# 16n.net
KiCad netlist of a schematic drawn in EAGLE
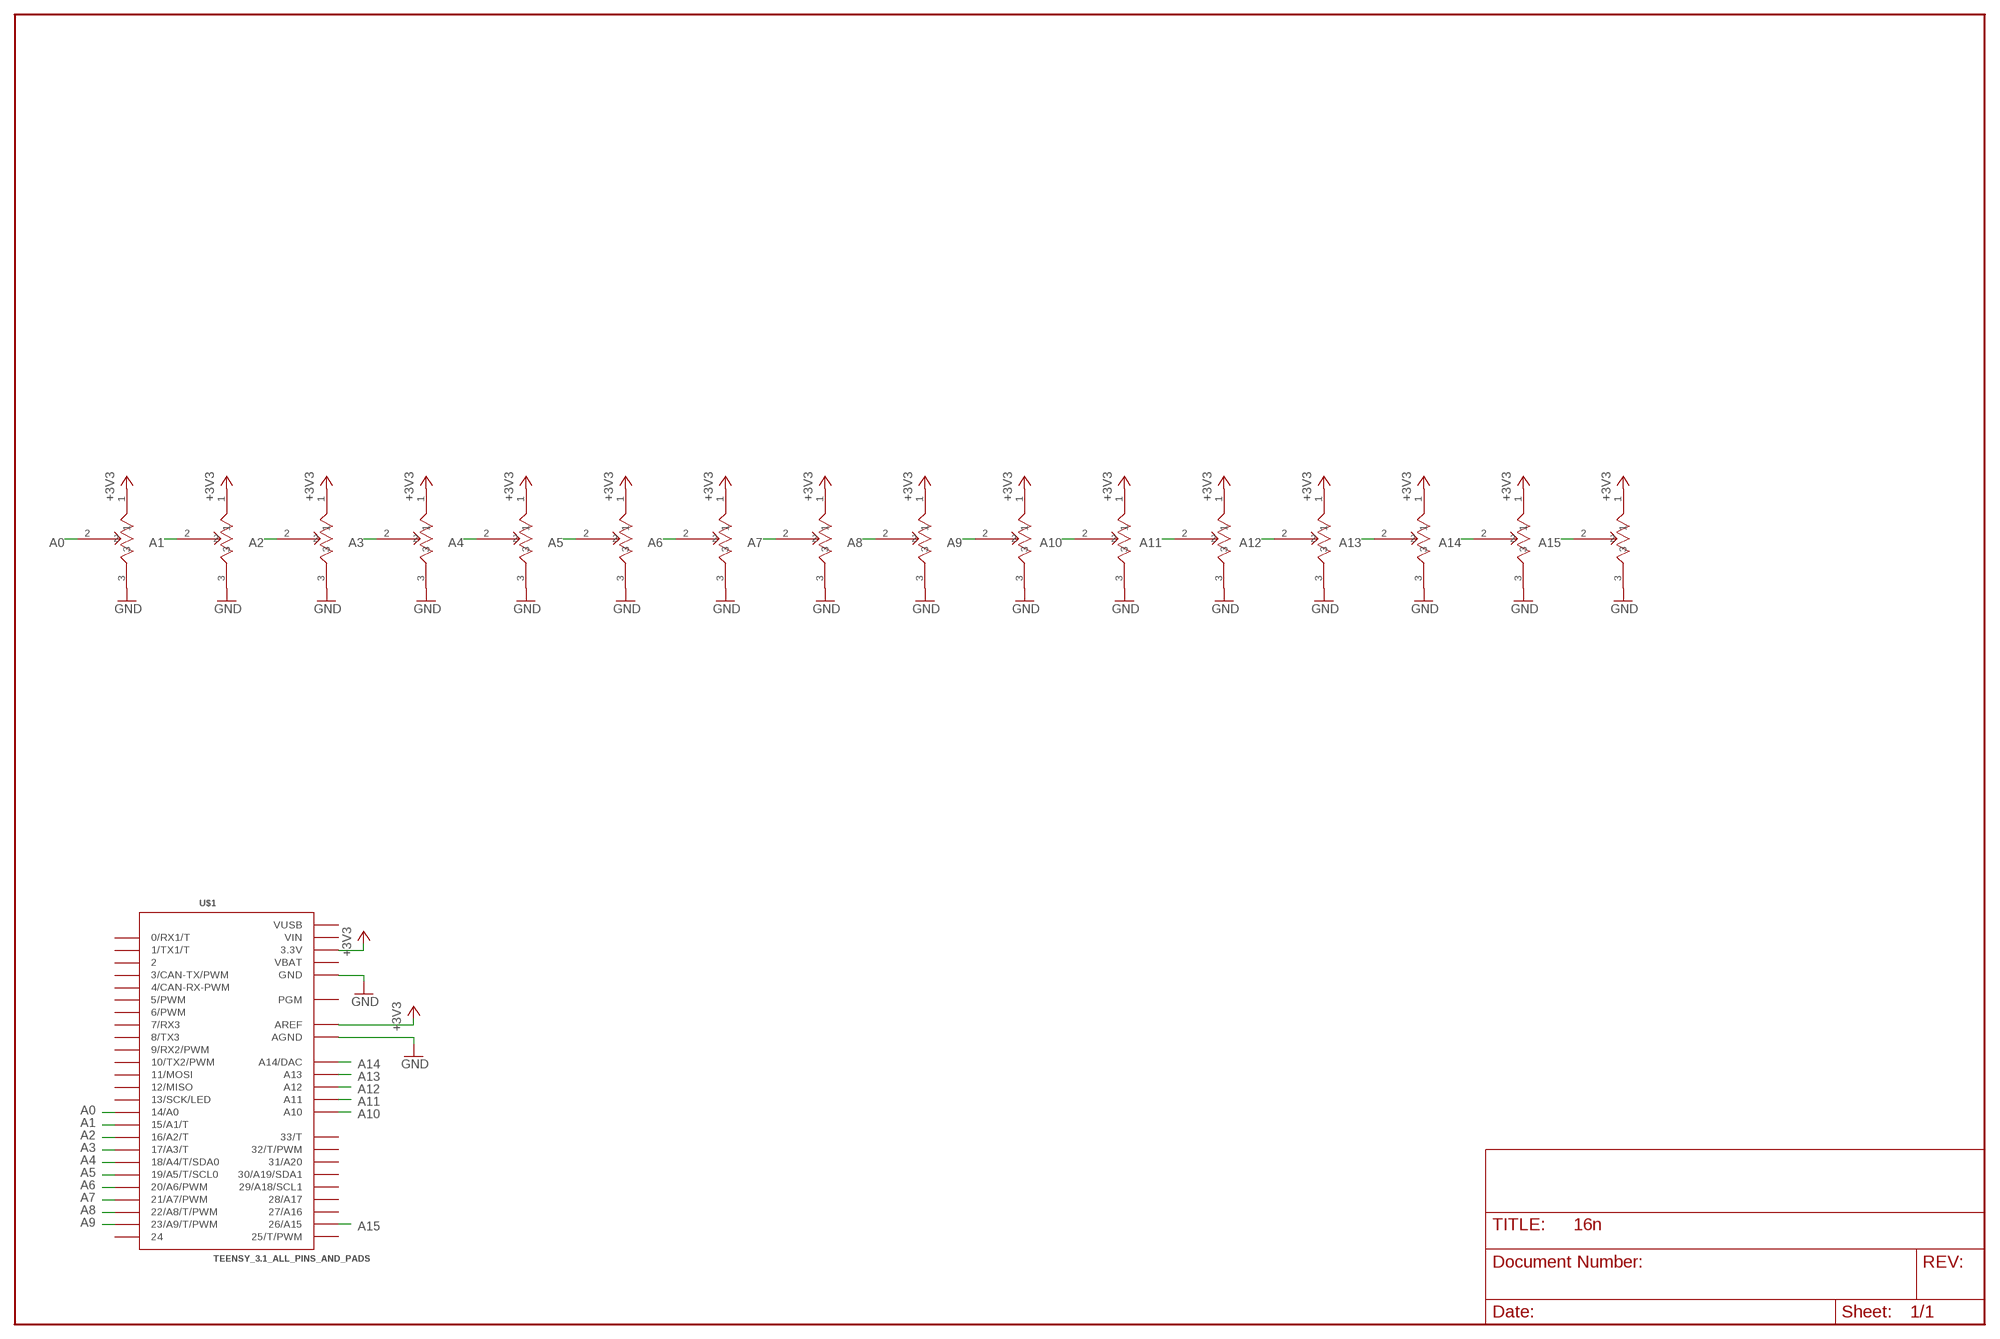
[diagram p0: schematic, sheet 1]

(export (version "E")
  (design (tool "Eeschema 10.0.6"))
  (components
    (comp (ref "U$1")
      (value "TEENSY_3.1_ALL_PINS_AND_PADS")
      (footprint "eagle-import:TEENSY_3.1_ALLPINS")
      (libsource (lib "eagle-import") (part "TEENSY_3.1_ALL_PINS_AND_PADS"))
    )
    (comp (ref "U$2")
      (value "SLIDEPOT-ALPS-60MM")
      (footprint "eagle-import:RS6011SP600")
      (libsource (lib "eagle-import") (part "SLIDEPOT-ALPS-60MM"))
    )
    (comp (ref "U$3")
      (value "SLIDEPOT-ALPS-60MM")
      (footprint "eagle-import:RS6011SP600")
      (libsource (lib "eagle-import") (part "SLIDEPOT-ALPS-60MM"))
    )
    (comp (ref "U$4")
      (value "SLIDEPOT-ALPS-60MM")
      (footprint "eagle-import:RS6011SP600")
      (libsource (lib "eagle-import") (part "SLIDEPOT-ALPS-60MM"))
    )
    (comp (ref "U$5")
      (value "SLIDEPOT-ALPS-60MM")
      (footprint "eagle-import:RS6011SP600")
      (libsource (lib "eagle-import") (part "SLIDEPOT-ALPS-60MM"))
    )
    (comp (ref "U$6")
      (value "SLIDEPOT-ALPS-60MM")
      (footprint "eagle-import:RS6011SP600")
      (libsource (lib "eagle-import") (part "SLIDEPOT-ALPS-60MM"))
    )
    (comp (ref "U$7")
      (value "SLIDEPOT-ALPS-60MM")
      (footprint "eagle-import:RS6011SP600")
      (libsource (lib "eagle-import") (part "SLIDEPOT-ALPS-60MM"))
    )
    (comp (ref "U$8")
      (value "SLIDEPOT-ALPS-60MM")
      (footprint "eagle-import:RS6011SP600")
      (libsource (lib "eagle-import") (part "SLIDEPOT-ALPS-60MM"))
    )
    (comp (ref "U$9")
      (value "SLIDEPOT-ALPS-60MM")
      (footprint "eagle-import:RS6011SP600")
      (libsource (lib "eagle-import") (part "SLIDEPOT-ALPS-60MM"))
    )
    (comp (ref "U$10")
      (value "SLIDEPOT-ALPS-60MM")
      (footprint "eagle-import:RS6011SP600")
      (libsource (lib "eagle-import") (part "SLIDEPOT-ALPS-60MM"))
    )
    (comp (ref "U$11")
      (value "SLIDEPOT-ALPS-60MM")
      (footprint "eagle-import:RS6011SP600")
      (libsource (lib "eagle-import") (part "SLIDEPOT-ALPS-60MM"))
    )
    (comp (ref "U$12")
      (value "SLIDEPOT-ALPS-60MM")
      (footprint "eagle-import:RS6011SP600")
      (libsource (lib "eagle-import") (part "SLIDEPOT-ALPS-60MM"))
    )
    (comp (ref "U$13")
      (value "SLIDEPOT-ALPS-60MM")
      (footprint "eagle-import:RS6011SP600")
      (libsource (lib "eagle-import") (part "SLIDEPOT-ALPS-60MM"))
    )
    (comp (ref "U$14")
      (value "SLIDEPOT-ALPS-60MM")
      (footprint "eagle-import:RS6011SP600")
      (libsource (lib "eagle-import") (part "SLIDEPOT-ALPS-60MM"))
    )
    (comp (ref "U$15")
      (value "SLIDEPOT-ALPS-60MM")
      (footprint "eagle-import:RS6011SP600")
      (libsource (lib "eagle-import") (part "SLIDEPOT-ALPS-60MM"))
    )
    (comp (ref "U$16")
      (value "SLIDEPOT-ALPS-60MM")
      (footprint "eagle-import:RS6011SP600")
      (libsource (lib "eagle-import") (part "SLIDEPOT-ALPS-60MM"))
    )
    (comp (ref "U$17")
      (value "SLIDEPOT-ALPS-60MM")
      (footprint "eagle-import:RS6011SP600")
      (libsource (lib "eagle-import") (part "SLIDEPOT-ALPS-60MM"))
    )
  )
  (nets
    (net (code "1") (name "+3V3") (class "Default")
      (node (ref "U$1") (pin "3.3V") (pinfunction "3.3V_3.3V") (pintype "power_in"))
      (node (ref "U$1") (pin "3.3V1") (pinfunction "3.3V_3.3V1") (pintype "power_in"))
      (node (ref "U$1") (pin "3.3V2") (pinfunction "3.3V_3.3V2") (pintype "power_in"))
      (node (ref "U$1") (pin "AREF") (pinfunction "AREF_AREF") (pintype "power_in"))
      (node (ref "U$10") (pin "1") (pinfunction "1_1") (pintype "bidirectional"))
      (node (ref "U$11") (pin "1") (pinfunction "1_1") (pintype "bidirectional"))
      (node (ref "U$12") (pin "1") (pinfunction "1_1") (pintype "bidirectional"))
      (node (ref "U$13") (pin "1") (pinfunction "1_1") (pintype "bidirectional"))
      (node (ref "U$14") (pin "1") (pinfunction "1_1") (pintype "bidirectional"))
      (node (ref "U$15") (pin "1") (pinfunction "1_1") (pintype "bidirectional"))
      (node (ref "U$16") (pin "1") (pinfunction "1_1") (pintype "bidirectional"))
      (node (ref "U$17") (pin "1") (pinfunction "1_1") (pintype "bidirectional"))
      (node (ref "U$2") (pin "1") (pinfunction "1_1") (pintype "bidirectional"))
      (node (ref "U$3") (pin "1") (pinfunction "1_1") (pintype "bidirectional"))
      (node (ref "U$4") (pin "1") (pinfunction "1_1") (pintype "bidirectional"))
      (node (ref "U$5") (pin "1") (pinfunction "1_1") (pintype "bidirectional"))
      (node (ref "U$6") (pin "1") (pinfunction "1_1") (pintype "bidirectional"))
      (node (ref "U$7") (pin "1") (pinfunction "1_1") (pintype "bidirectional"))
      (node (ref "U$8") (pin "1") (pinfunction "1_1") (pintype "bidirectional"))
      (node (ref "U$9") (pin "1") (pinfunction "1_1") (pintype "bidirectional"))
    )
    (net (code "2") (name "/A0") (class "Default")
      (node (ref "U$1") (pin "14/A0") (pinfunction "14/A0_14/A0") (pintype "bidirectional"))
      (node (ref "U$2") (pin "2") (pinfunction "2_2") (pintype "bidirectional"))
    )
    (net (code "3") (name "/A1") (class "Default")
      (node (ref "U$1") (pin "15/A1") (pinfunction "15/A1/T_15/A1") (pintype "bidirectional"))
      (node (ref "U$3") (pin "2") (pinfunction "2_2") (pintype "bidirectional"))
    )
    (net (code "4") (name "/A2") (class "Default")
      (node (ref "U$1") (pin "16/A2") (pinfunction "16/A2/T_16/A2") (pintype "bidirectional"))
      (node (ref "U$4") (pin "2") (pinfunction "2_2") (pintype "bidirectional"))
    )
    (net (code "5") (name "/A3") (class "Default")
      (node (ref "U$1") (pin "17/A3") (pinfunction "17/A3/T_17/A3") (pintype "bidirectional"))
      (node (ref "U$5") (pin "2") (pinfunction "2_2") (pintype "bidirectional"))
    )
    (net (code "6") (name "/A4") (class "Default")
      (node (ref "U$1") (pin "18/A4") (pinfunction "18/A4/T/SDA0_18/A4") (pintype "bidirectional"))
      (node (ref "U$6") (pin "2") (pinfunction "2_2") (pintype "bidirectional"))
    )
    (net (code "7") (name "/A5") (class "Default")
      (node (ref "U$1") (pin "19/A5") (pinfunction "19/A5/T/SCL0_19/A5") (pintype "bidirectional"))
      (node (ref "U$7") (pin "2") (pinfunction "2_2") (pintype "bidirectional"))
    )
    (net (code "8") (name "/A6") (class "Default")
      (node (ref "U$1") (pin "20/A6") (pinfunction "20/A6/PWM_20/A6") (pintype "bidirectional"))
      (node (ref "U$8") (pin "2") (pinfunction "2_2") (pintype "bidirectional"))
    )
    (net (code "9") (name "/A7") (class "Default")
      (node (ref "U$1") (pin "21/A7") (pinfunction "21/A7/PWM_21/A7") (pintype "bidirectional"))
      (node (ref "U$9") (pin "2") (pinfunction "2_2") (pintype "bidirectional"))
    )
    (net (code "10") (name "/A8") (class "Default")
      (node (ref "U$1") (pin "22/A8") (pinfunction "22/A8/T/PWM_22/A8") (pintype "bidirectional"))
      (node (ref "U$10") (pin "2") (pinfunction "2_2") (pintype "bidirectional"))
    )
    (net (code "11") (name "/A9") (class "Default")
      (node (ref "U$1") (pin "23/A9") (pinfunction "23/A9/T/PWM_23/A9") (pintype "bidirectional"))
      (node (ref "U$11") (pin "2") (pinfunction "2_2") (pintype "bidirectional"))
    )
    (net (code "12") (name "/A10") (class "Default")
      (node (ref "U$1") (pin "A10") (pinfunction "A10_A10") (pintype "bidirectional"))
      (node (ref "U$12") (pin "2") (pinfunction "2_2") (pintype "bidirectional"))
    )
    (net (code "13") (name "/A11") (class "Default")
      (node (ref "U$1") (pin "A11") (pinfunction "A11_A11") (pintype "bidirectional"))
      (node (ref "U$13") (pin "2") (pinfunction "2_2") (pintype "bidirectional"))
    )
    (net (code "14") (name "/A12") (class "Default")
      (node (ref "U$1") (pin "A12") (pinfunction "A12_A12") (pintype "bidirectional"))
      (node (ref "U$14") (pin "2") (pinfunction "2_2") (pintype "bidirectional"))
    )
    (net (code "15") (name "/A13") (class "Default")
      (node (ref "U$1") (pin "A13") (pinfunction "A13_A13") (pintype "bidirectional"))
      (node (ref "U$15") (pin "2") (pinfunction "2_2") (pintype "bidirectional"))
    )
    (net (code "16") (name "/A14") (class "Default")
      (node (ref "U$1") (pin "A14") (pinfunction "A14/DAC_A14") (pintype "bidirectional"))
      (node (ref "U$16") (pin "2") (pinfunction "2_2") (pintype "bidirectional"))
    )
    (net (code "17") (name "/A15") (class "Default")
      (node (ref "U$1") (pin "26") (pinfunction "26/A15_26") (pintype "bidirectional"))
      (node (ref "U$17") (pin "2") (pinfunction "2_2") (pintype "bidirectional"))
    )
    (net (code "18") (name "/VBAT") (class "Default")
      (node (ref "U$1") (pin "VBAT") (pinfunction "VBAT_VBAT") (pintype "power_in"))
    )
    (net (code "19") (name "/VIN") (class "Default")
      (node (ref "U$1") (pin "VIN") (pinfunction "VIN_VIN") (pintype "power_in"))
    )
    (net (code "20") (name "/VUSB") (class "Default")
      (node (ref "U$1") (pin "VUSB") (pinfunction "VUSB_VUSB") (pintype "power_in"))
    )
    (net (code "21") (name "GND") (class "Default")
      (node (ref "U$1") (pin "AGND") (pinfunction "AGND_AGND") (pintype "power_in"))
      (node (ref "U$1") (pin "GND") (pinfunction "GND_GND") (pintype "power_in"))
      (node (ref "U$1") (pin "GND1") (pinfunction "GND_GND1") (pintype "power_in"))
      (node (ref "U$1") (pin "GND2") (pinfunction "GND_GND2") (pintype "power_in"))
      (node (ref "U$10") (pin "3") (pinfunction "3_3") (pintype "bidirectional"))
      (node (ref "U$11") (pin "3") (pinfunction "3_3") (pintype "bidirectional"))
      (node (ref "U$12") (pin "3") (pinfunction "3_3") (pintype "bidirectional"))
      (node (ref "U$13") (pin "3") (pinfunction "3_3") (pintype "bidirectional"))
      (node (ref "U$14") (pin "3") (pinfunction "3_3") (pintype "bidirectional"))
      (node (ref "U$15") (pin "3") (pinfunction "3_3") (pintype "bidirectional"))
      (node (ref "U$16") (pin "3") (pinfunction "3_3") (pintype "bidirectional"))
      (node (ref "U$17") (pin "3") (pinfunction "3_3") (pintype "bidirectional"))
      (node (ref "U$2") (pin "3") (pinfunction "3_3") (pintype "bidirectional"))
      (node (ref "U$3") (pin "3") (pinfunction "3_3") (pintype "bidirectional"))
      (node (ref "U$4") (pin "3") (pinfunction "3_3") (pintype "bidirectional"))
      (node (ref "U$5") (pin "3") (pinfunction "3_3") (pintype "bidirectional"))
      (node (ref "U$6") (pin "3") (pinfunction "3_3") (pintype "bidirectional"))
      (node (ref "U$7") (pin "3") (pinfunction "3_3") (pintype "bidirectional"))
      (node (ref "U$8") (pin "3") (pinfunction "3_3") (pintype "bidirectional"))
      (node (ref "U$9") (pin "3") (pinfunction "3_3") (pintype "bidirectional"))
    )
    (net (code "22") (name "unconnected-(U$1-0{slash}RX1{slash}T-Pad0)") (class "Default")
      (node (ref "U$1") (pin "0") (pinfunction "0/RX1/T_0") (pintype "bidirectional"))
    )
    (net (code "23") (name "unconnected-(U$1-1{slash}TX1{slash}T-Pad1)") (class "Default")
      (node (ref "U$1") (pin "1") (pinfunction "1/TX1/T_1") (pintype "bidirectional"))
    )
    (net (code "24") (name "unconnected-(U$1-3{slash}CAN-TX{slash}PWM-Pad3)") (class "Default")
      (node (ref "U$1") (pin "3") (pinfunction "3/CAN-TX/PWM_3") (pintype "bidirectional"))
    )
    (net (code "25") (name "unconnected-(U$1-4{slash}CAN-RX-PWM-Pad4)") (class "Default")
      (node (ref "U$1") (pin "4") (pinfunction "4/CAN-RX-PWM_4") (pintype "bidirectional"))
    )
    (net (code "26") (name "unconnected-(U$1-5{slash}PWM-Pad5)") (class "Default")
      (node (ref "U$1") (pin "5") (pinfunction "5/PWM_5") (pintype "bidirectional"))
    )
    (net (code "27") (name "unconnected-(U$1-6{slash}PWM-Pad6)") (class "Default")
      (node (ref "U$1") (pin "6") (pinfunction "6/PWM_6") (pintype "bidirectional"))
    )
    (net (code "28") (name "unconnected-(U$1-7{slash}RX3-Pad7)") (class "Default")
      (node (ref "U$1") (pin "7") (pinfunction "7/RX3_7") (pintype "bidirectional"))
    )
    (net (code "29") (name "unconnected-(U$1-8{slash}TX3-Pad8)") (class "Default")
      (node (ref "U$1") (pin "8") (pinfunction "8/TX3_8") (pintype "bidirectional"))
    )
    (net (code "30") (name "unconnected-(U$1-9{slash}RX2{slash}PWM-Pad9)") (class "Default")
      (node (ref "U$1") (pin "9") (pinfunction "9/RX2/PWM_9") (pintype "bidirectional"))
    )
    (net (code "31") (name "unconnected-(U$1-10{slash}TX2{slash}PWM-Pad10)") (class "Default")
      (node (ref "U$1") (pin "10") (pinfunction "10/TX2/PWM_10") (pintype "bidirectional"))
    )
    (net (code "32") (name "unconnected-(U$1-11{slash}MOSI-Pad11)") (class "Default")
      (node (ref "U$1") (pin "11") (pinfunction "11/MOSI_11") (pintype "bidirectional"))
    )
    (net (code "33") (name "unconnected-(U$1-12{slash}MISO-Pad12)") (class "Default")
      (node (ref "U$1") (pin "12") (pinfunction "12/MISO_12") (pintype "bidirectional"))
    )
    (net (code "34") (name "unconnected-(U$1-13{slash}SCK{slash}LED-Pad13)") (class "Default")
      (node (ref "U$1") (pin "13") (pinfunction "13/SCK/LED_13") (pintype "bidirectional"))
    )
    (net (code "35") (name "unconnected-(U$1-25{slash}T{slash}PWM-Pad25)") (class "Default")
      (node (ref "U$1") (pin "25") (pinfunction "25/T/PWM_25") (pintype "bidirectional"))
    )
    (net (code "36") (name "unconnected-(U$1-27{slash}A16-Pad27)") (class "Default")
      (node (ref "U$1") (pin "27") (pinfunction "27/A16_27") (pintype "bidirectional"))
    )
    (net (code "37") (name "unconnected-(U$1-28{slash}A17-Pad28)") (class "Default")
      (node (ref "U$1") (pin "28") (pinfunction "28/A17_28") (pintype "bidirectional"))
    )
    (net (code "38") (name "unconnected-(U$1-29{slash}A18{slash}SCL1-Pad29)") (class "Default")
      (node (ref "U$1") (pin "29") (pinfunction "29/A18/SCL1_29") (pintype "bidirectional"))
    )
    (net (code "39") (name "unconnected-(U$1-30{slash}A19{slash}SDA1-Pad30)") (class "Default")
      (node (ref "U$1") (pin "30") (pinfunction "30/A19/SDA1_30") (pintype "bidirectional"))
    )
    (net (code "40") (name "unconnected-(U$1-31{slash}A20-Pad31)") (class "Default")
      (node (ref "U$1") (pin "31") (pinfunction "31/A20_31") (pintype "bidirectional"))
    )
    (net (code "41") (name "unconnected-(U$1-32{slash}T{slash}PWM-Pad32)") (class "Default")
      (node (ref "U$1") (pin "32") (pinfunction "32/T/PWM_32") (pintype "bidirectional"))
    )
    (net (code "42") (name "unconnected-(U$1-33{slash}T-Pad33)") (class "Default")
      (node (ref "U$1") (pin "33") (pinfunction "33/T_33") (pintype "bidirectional"))
    )
    (net (code "43") (name "unconnected-(U$1-Pad2)") (class "Default")
      (node (ref "U$1") (pin "2") (pinfunction "2_2") (pintype "bidirectional"))
    )
    (net (code "44") (name "unconnected-(U$1-Pad24)") (class "Default")
      (node (ref "U$1") (pin "24") (pinfunction "24_24") (pintype "bidirectional"))
    )
    (net (code "45") (name "unconnected-(U$1-PadPGM)") (class "Default")
      (node (ref "U$1") (pin "PGM") (pinfunction "PGM_PGM") (pintype "bidirectional"))
    )
  )
)
